# ParallelJoysticks.net
KiCad netlist of a schematic drawn in Altium Designer
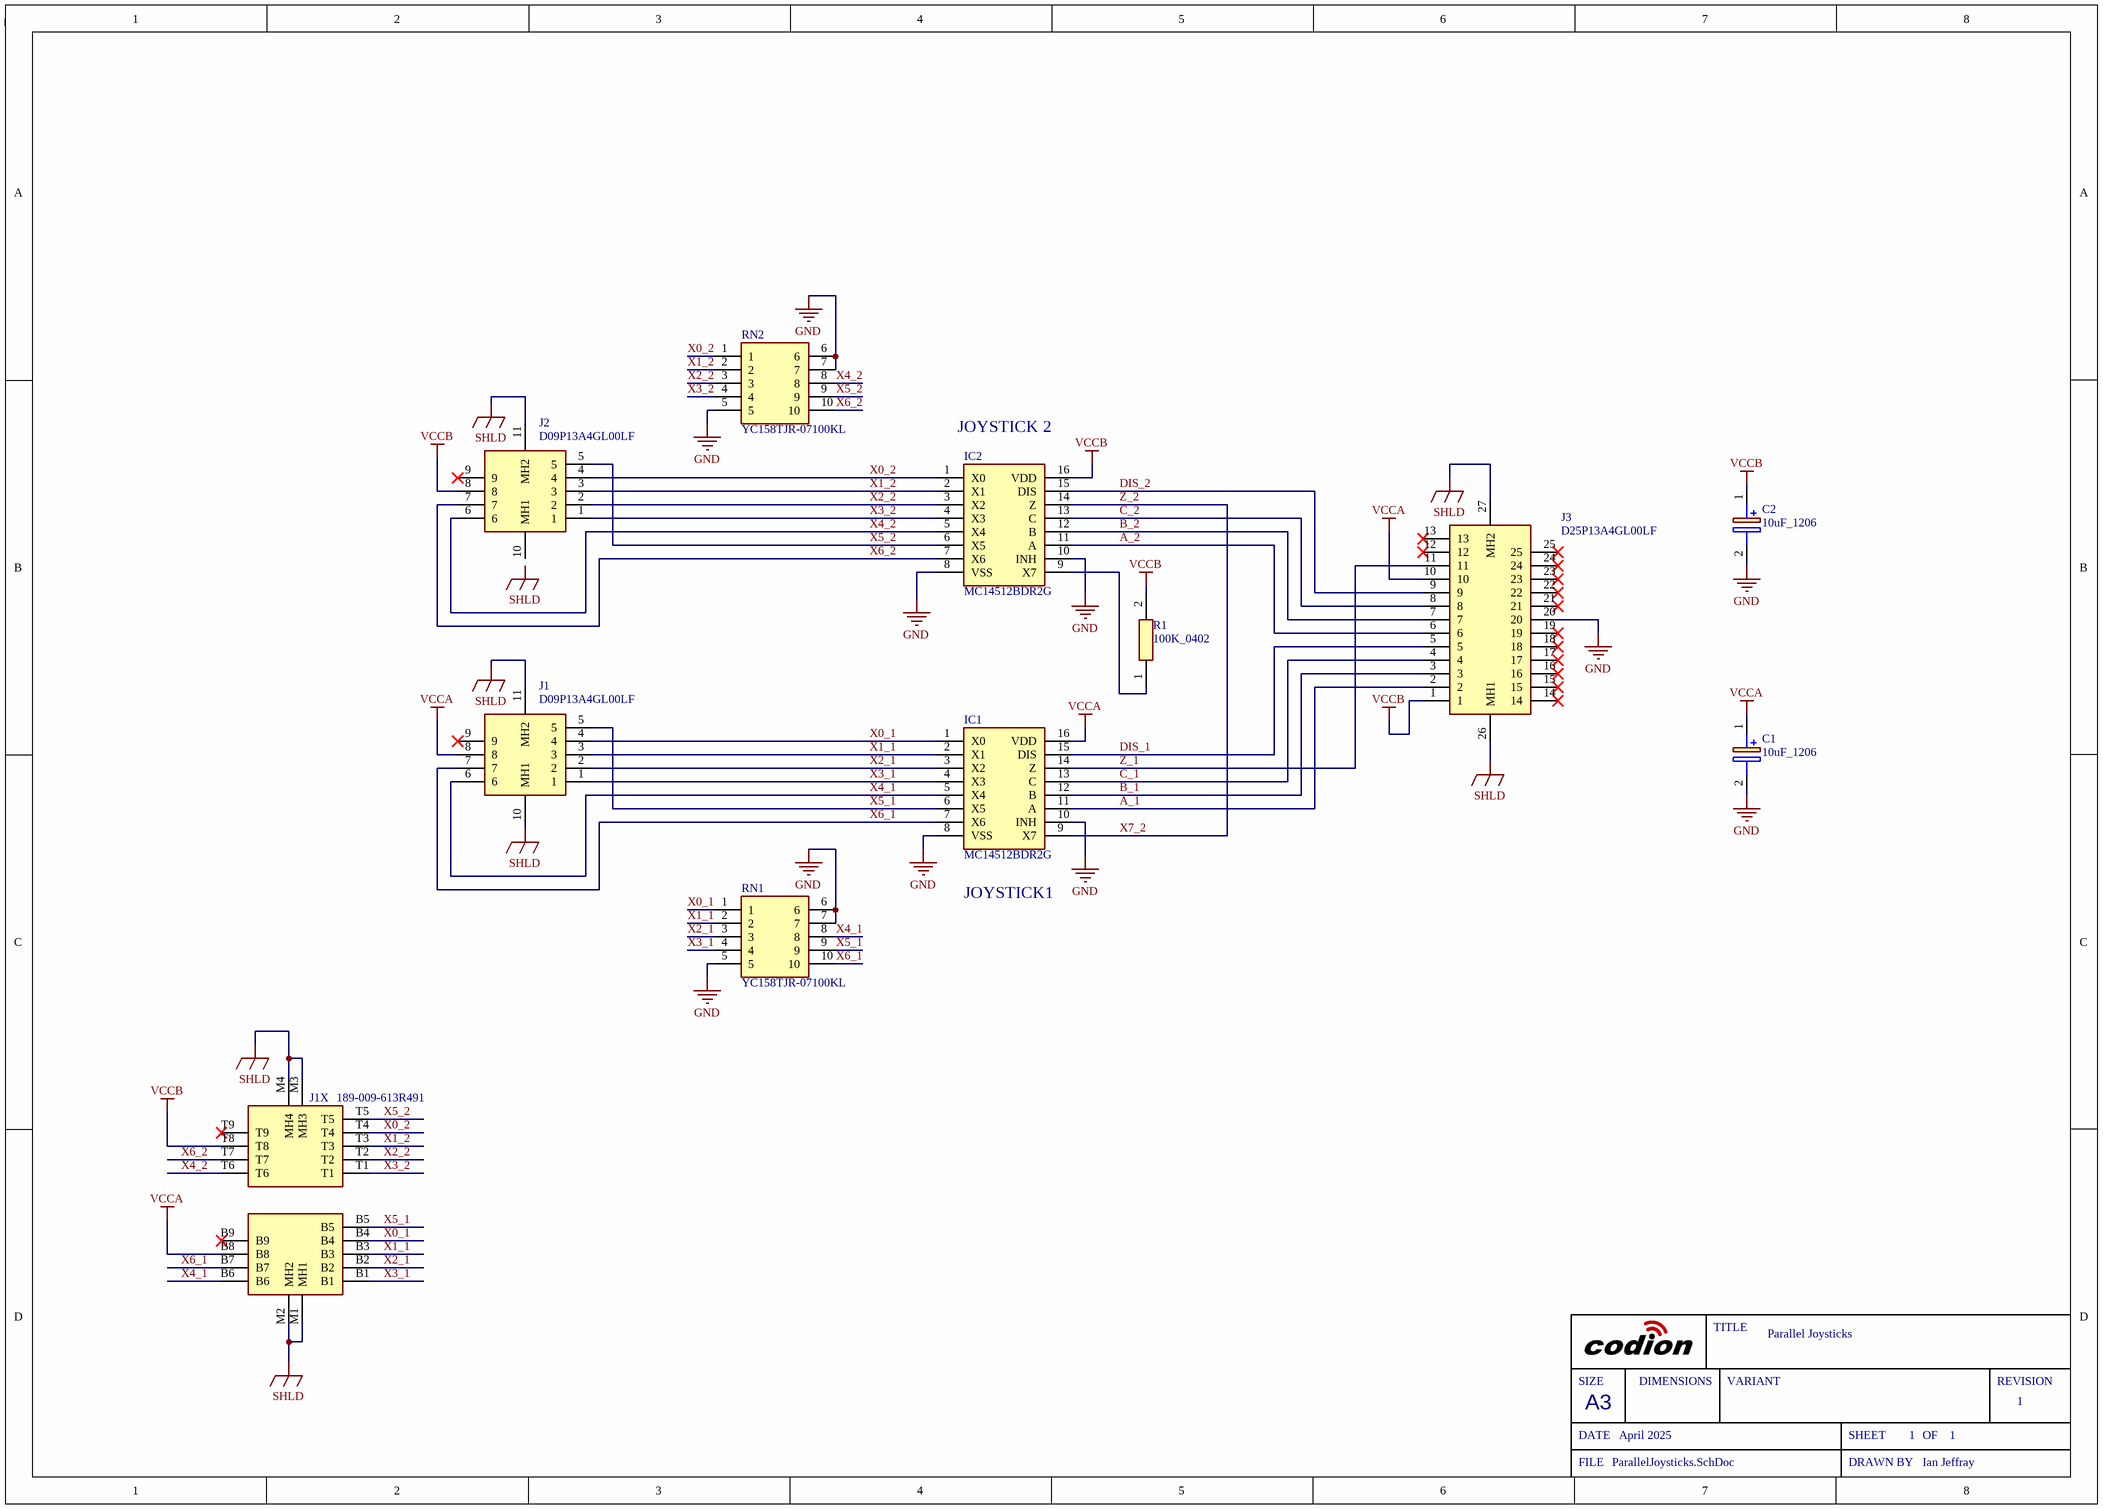
[diagram p0: ParallelJoysticks.SchDoc]

(export (version "E")
  (design (tool "Eeschema 10.0.6"))
  (components
    (comp (ref "C1")
      (value "10uF_1206")
      (footprint "SamacSys:CAPPM3216X180N")
      (description "Capacitor Polarised")
      (fields
        (field (name "MANUFACTURER_PART_NUMBER") "TAJA106M010RNJ")
        (field (name "MOUSER PART NUMBER") "581-TAJA106M010R")
      )
      (libsource (lib "*") (part "TAJA106M010RNJ"))
    )
    (comp (ref "C2")
      (value "10uF_1206")
      (footprint "SamacSys:CAPPM3216X180N")
      (description "Capacitor Polarised")
      (fields
        (field (name "MANUFACTURER_PART_NUMBER") "TAJA106M010RNJ")
        (field (name "MOUSER PART NUMBER") "581-TAJA106M010R")
      )
      (libsource (lib "*") (part "TAJA106M010RNJ"))
    )
    (comp (ref "IC1")
      (value "MC14512BDR2G")
      (footprint "SamacSys:SOIC127P600X175-16N")
      (description "Integrated Circuit")
      (fields (field (name "MOUSER PART NUMBER") "863-MC14512BDR2G"))
      (libsource (lib "*") (part "MC14512BDR2G"))
    )
    (comp (ref "IC2")
      (value "MC14512BDR2G")
      (footprint "SamacSys:SOIC127P600X175-16N")
      (description "Integrated Circuit")
      (fields (field (name "MOUSER PART NUMBER") "863-MC14512BDR2G"))
      (libsource (lib "*") (part "MC14512BDR2G"))
    )
    (comp (ref "J1")
      (value "D09P13A4GL00LF")
      (footprint "SamacSys:D09P13A4GV00LF")
      (description "Connector")
      (libsource (lib "*") (part "D09P13A4GV00LF"))
    )
    (comp (ref "J1X")
      (value "189-009-613R491")
      (footprint "189-009-613R491")
      (description "Connector")
      (libsource (lib "Acorn") (part "189-009-613R491"))
    )
    (comp (ref "J2")
      (value "D09P13A4GL00LF")
      (footprint "SamacSys:D09P13A4GV00LF")
      (description "Connector")
      (libsource (lib "*") (part "D09P13A4GV00LF"))
    )
    (comp (ref "J3")
      (value "D25P13A4GL00LF")
      (footprint "SamacSys:D25P13A4GV00LF")
      (description "Connector")
      (libsource (lib "*") (part "D25P13A4GV00LF"))
    )
    (comp (ref "R1")
      (value "100K_0402")
      (footprint "SamacSys:RESC1005X40N")
      (description "Resistor")
      (fields
        (field (name "MANUFACTURER_PART_NUMBER") "CRCW0402100KFKEDHP")
        (field (name "MOUSER PART NUMBER") "71-CRCW0402100KFKEDH")
      )
      (libsource (lib "*") (part "CRCW0402100KFKEDHP"))
    )
    (comp (ref "RN1")
      (value "YC158TJR-07100KL")
      (footprint "SamacSys:YC158TJR07100KL")
      (description "Resistor Network")
      (fields (field (name "MOUSER PART NUMBER") "603-YC158TJR-07100KL"))
      (libsource (lib "*") (part "YC158TJR-07100KL"))
    )
    (comp (ref "RN2")
      (value "YC158TJR-07100KL")
      (footprint "SamacSys:YC158TJR07100KL")
      (description "Resistor Network")
      (fields (field (name "MOUSER PART NUMBER") "603-YC158TJR-07100KL"))
      (libsource (lib "*") (part "YC158TJR-07100KL"))
    )
  )
  (nets
    (net (code "1") (name "/A_1") (class "Default")
      (node (ref "IC1") (pin "11") (pinfunction "A_11") (pintype "passive"))
      (node (ref "J3") (pin "2") (pinfunction "2_2") (pintype "passive"))
    )
    (net (code "2") (name "/A_2") (class "Default")
      (node (ref "IC2") (pin "11") (pinfunction "A_11") (pintype "passive"))
      (node (ref "J3") (pin "6") (pinfunction "6_6") (pintype "passive"))
    )
    (net (code "3") (name "/B_1") (class "Default")
      (node (ref "IC1") (pin "12") (pinfunction "B_12") (pintype "passive"))
      (node (ref "J3") (pin "3") (pinfunction "3_3") (pintype "passive"))
    )
    (net (code "4") (name "/B_2") (class "Default")
      (node (ref "IC2") (pin "12") (pinfunction "B_12") (pintype "passive"))
      (node (ref "J3") (pin "7") (pinfunction "7_7") (pintype "passive"))
    )
    (net (code "5") (name "/C_1") (class "Default")
      (node (ref "IC1") (pin "13") (pinfunction "C_13") (pintype "passive"))
      (node (ref "J3") (pin "4") (pinfunction "4_4") (pintype "passive"))
    )
    (net (code "6") (name "/C_2") (class "Default")
      (node (ref "IC2") (pin "13") (pinfunction "C_13") (pintype "passive"))
      (node (ref "J3") (pin "8") (pinfunction "8_8") (pintype "passive"))
    )
    (net (code "7") (name "/DIS_1") (class "Default")
      (node (ref "IC1") (pin "15") (pinfunction "DIS_15") (pintype "passive"))
      (node (ref "J3") (pin "5") (pinfunction "5_5") (pintype "passive"))
    )
    (net (code "8") (name "/DIS_2") (class "Default")
      (node (ref "IC2") (pin "15") (pinfunction "DIS_15") (pintype "passive"))
      (node (ref "J3") (pin "9") (pinfunction "9_9") (pintype "passive"))
    )
    (net (code "9") (name "/X0_1") (class "Default")
      (node (ref "IC1") (pin "1") (pinfunction "X0_1") (pintype "passive"))
      (node (ref "J1") (pin "4") (pinfunction "4_4") (pintype "passive"))
      (node (ref "J1X") (pin "B4") (pinfunction "B4_B4") (pintype "passive"))
      (node (ref "RN1") (pin "1") (pinfunction "1_1") (pintype "passive"))
    )
    (net (code "10") (name "/X0_2") (class "Default")
      (node (ref "IC2") (pin "1") (pinfunction "X0_1") (pintype "passive"))
      (node (ref "J1X") (pin "T4") (pinfunction "T4_T4") (pintype "passive"))
      (node (ref "J2") (pin "4") (pinfunction "4_4") (pintype "passive"))
      (node (ref "RN2") (pin "1") (pinfunction "1_1") (pintype "passive"))
    )
    (net (code "11") (name "/X1_1") (class "Default")
      (node (ref "IC1") (pin "2") (pinfunction "X1_2") (pintype "passive"))
      (node (ref "J1") (pin "3") (pinfunction "3_3") (pintype "passive"))
      (node (ref "J1X") (pin "B3") (pinfunction "B3_B3") (pintype "passive"))
      (node (ref "RN1") (pin "2") (pinfunction "2_2") (pintype "passive"))
    )
    (net (code "12") (name "/X1_2") (class "Default")
      (node (ref "IC2") (pin "2") (pinfunction "X1_2") (pintype "passive"))
      (node (ref "J1X") (pin "T3") (pinfunction "T3_T3") (pintype "passive"))
      (node (ref "J2") (pin "3") (pinfunction "3_3") (pintype "passive"))
      (node (ref "RN2") (pin "2") (pinfunction "2_2") (pintype "passive"))
    )
    (net (code "13") (name "/X2_1") (class "Default")
      (node (ref "IC1") (pin "3") (pinfunction "X2_3") (pintype "passive"))
      (node (ref "J1") (pin "2") (pinfunction "2_2") (pintype "passive"))
      (node (ref "J1X") (pin "B2") (pinfunction "B2_B2") (pintype "passive"))
      (node (ref "RN1") (pin "3") (pinfunction "3_3") (pintype "passive"))
    )
    (net (code "14") (name "/X2_2") (class "Default")
      (node (ref "IC2") (pin "3") (pinfunction "X2_3") (pintype "passive"))
      (node (ref "J1X") (pin "T2") (pinfunction "T2_T2") (pintype "passive"))
      (node (ref "J2") (pin "2") (pinfunction "2_2") (pintype "passive"))
      (node (ref "RN2") (pin "3") (pinfunction "3_3") (pintype "passive"))
    )
    (net (code "15") (name "/X3_1") (class "Default")
      (node (ref "IC1") (pin "4") (pinfunction "X3_4") (pintype "passive"))
      (node (ref "J1") (pin "1") (pinfunction "1_1") (pintype "passive"))
      (node (ref "J1X") (pin "B1") (pinfunction "B1_B1") (pintype "passive"))
      (node (ref "RN1") (pin "4") (pinfunction "4_4") (pintype "passive"))
    )
    (net (code "16") (name "/X3_2") (class "Default")
      (node (ref "IC2") (pin "4") (pinfunction "X3_4") (pintype "passive"))
      (node (ref "J1X") (pin "T1") (pinfunction "T1_T1") (pintype "passive"))
      (node (ref "J2") (pin "1") (pinfunction "1_1") (pintype "passive"))
      (node (ref "RN2") (pin "4") (pinfunction "4_4") (pintype "passive"))
    )
    (net (code "17") (name "/X4_1") (class "Default")
      (node (ref "IC1") (pin "5") (pinfunction "X4_5") (pintype "passive"))
      (node (ref "J1") (pin "6") (pinfunction "6_6") (pintype "passive"))
      (node (ref "J1X") (pin "B6") (pinfunction "B6_B6") (pintype "passive"))
      (node (ref "RN1") (pin "8") (pinfunction "8_8") (pintype "passive"))
    )
    (net (code "18") (name "/X4_2") (class "Default")
      (node (ref "IC2") (pin "5") (pinfunction "X4_5") (pintype "passive"))
      (node (ref "J1X") (pin "T6") (pinfunction "T6_T6") (pintype "passive"))
      (node (ref "J2") (pin "6") (pinfunction "6_6") (pintype "passive"))
      (node (ref "RN2") (pin "8") (pinfunction "8_8") (pintype "passive"))
    )
    (net (code "19") (name "/X5_1") (class "Default")
      (node (ref "IC1") (pin "6") (pinfunction "X5_6") (pintype "passive"))
      (node (ref "J1") (pin "5") (pinfunction "5_5") (pintype "passive"))
      (node (ref "J1X") (pin "B5") (pinfunction "B5_B5") (pintype "passive"))
      (node (ref "RN1") (pin "9") (pinfunction "9_9") (pintype "passive"))
    )
    (net (code "20") (name "/X5_2") (class "Default")
      (node (ref "IC2") (pin "6") (pinfunction "X5_6") (pintype "passive"))
      (node (ref "J1X") (pin "T5") (pinfunction "T5_T5") (pintype "passive"))
      (node (ref "J2") (pin "5") (pinfunction "5_5") (pintype "passive"))
      (node (ref "RN2") (pin "9") (pinfunction "9_9") (pintype "passive"))
    )
    (net (code "21") (name "/X6_1") (class "Default")
      (node (ref "IC1") (pin "7") (pinfunction "X6_7") (pintype "passive"))
      (node (ref "J1") (pin "7") (pinfunction "7_7") (pintype "passive"))
      (node (ref "J1X") (pin "B7") (pinfunction "B7_B7") (pintype "passive"))
      (node (ref "RN1") (pin "10") (pinfunction "10_10") (pintype "passive"))
    )
    (net (code "22") (name "/X6_2") (class "Default")
      (node (ref "IC2") (pin "7") (pinfunction "X6_7") (pintype "passive"))
      (node (ref "J1X") (pin "T7") (pinfunction "T7_T7") (pintype "passive"))
      (node (ref "J2") (pin "7") (pinfunction "7_7") (pintype "passive"))
      (node (ref "RN2") (pin "10") (pinfunction "10_10") (pintype "passive"))
    )
    (net (code "23") (name "/X7_2") (class "Default")
      (node (ref "IC1") (pin "9") (pinfunction "X7_9") (pintype "passive"))
      (node (ref "IC2") (pin "14") (pinfunction "Z_14") (pintype "passive"))
    )
    (net (code "24") (name "/Z_1") (class "Default")
      (node (ref "IC1") (pin "14") (pinfunction "Z_14") (pintype "passive"))
      (node (ref "J3") (pin "11") (pinfunction "11_11") (pintype "passive"))
    )
    (net (code "25") (name "GND") (class "Default")
      (node (ref "C1") (pin "2") (pinfunction "-_2") (pintype "passive"))
      (node (ref "C2") (pin "2") (pinfunction "-_2") (pintype "passive"))
      (node (ref "IC1") (pin "10") (pinfunction "INH_10") (pintype "passive"))
      (node (ref "IC1") (pin "8") (pinfunction "VSS_8") (pintype "passive"))
      (node (ref "IC2") (pin "10") (pinfunction "INH_10") (pintype "passive"))
      (node (ref "IC2") (pin "8") (pinfunction "VSS_8") (pintype "passive"))
      (node (ref "J3") (pin "20") (pinfunction "20_20") (pintype "passive"))
      (node (ref "RN1") (pin "5") (pinfunction "5_5") (pintype "passive"))
      (node (ref "RN1") (pin "6") (pinfunction "6_6") (pintype "passive"))
      (node (ref "RN1") (pin "7") (pinfunction "7_7") (pintype "passive"))
      (node (ref "RN2") (pin "5") (pinfunction "5_5") (pintype "passive"))
      (node (ref "RN2") (pin "6") (pinfunction "6_6") (pintype "passive"))
      (node (ref "RN2") (pin "7") (pinfunction "7_7") (pintype "passive"))
    )
    (net (code "26") (name "Net-(IC2-X7)") (class "Default")
      (node (ref "IC2") (pin "9") (pinfunction "X7_9") (pintype "passive"))
      (node (ref "R1") (pin "1") (pinfunction "1_1") (pintype "passive"))
    )
    (net (code "27") (name "SHLD") (class "Default")
      (node (ref "J1") (pin "10") (pinfunction "MH1_10") (pintype "passive"))
      (node (ref "J1") (pin "11") (pinfunction "MH2_11") (pintype "passive"))
      (node (ref "J1X") (pin "M1") (pinfunction "MH1_M1") (pintype "passive"))
      (node (ref "J1X") (pin "M2") (pinfunction "MH2_M2") (pintype "passive"))
      (node (ref "J1X") (pin "M3") (pinfunction "MH3_M3") (pintype "passive"))
      (node (ref "J1X") (pin "M4") (pinfunction "MH4_M4") (pintype "passive"))
      (node (ref "J2") (pin "11") (pinfunction "MH2_11") (pintype "passive"))
      (node (ref "J3") (pin "26") (pinfunction "MH1_26") (pintype "passive"))
      (node (ref "J3") (pin "27") (pinfunction "MH2_27") (pintype "passive"))
    )
    (net (code "28") (name "VCCA") (class "Default")
      (node (ref "C1") (pin "1") (pinfunction "+_1") (pintype "passive"))
      (node (ref "IC1") (pin "16") (pinfunction "VDD_16") (pintype "passive"))
      (node (ref "J1") (pin "8") (pinfunction "8_8") (pintype "passive"))
      (node (ref "J1X") (pin "B8") (pinfunction "B8_B8") (pintype "passive"))
      (node (ref "J3") (pin "10") (pinfunction "10_10") (pintype "passive"))
    )
    (net (code "29") (name "VCCB") (class "Default")
      (node (ref "C2") (pin "1") (pinfunction "+_1") (pintype "passive"))
      (node (ref "IC2") (pin "16") (pinfunction "VDD_16") (pintype "passive"))
      (node (ref "J1X") (pin "T8") (pinfunction "T8_T8") (pintype "passive"))
      (node (ref "J2") (pin "8") (pinfunction "8_8") (pintype "passive"))
      (node (ref "J3") (pin "1") (pinfunction "1_1") (pintype "passive"))
      (node (ref "R1") (pin "2") (pinfunction "2_2") (pintype "passive"))
    )
    (net (code "30") (name "unconnected-(J1-Pad9)") (class "Default")
      (node (ref "J1") (pin "9") (pinfunction "9_9") (pintype "passive+no_connect"))
    )
    (net (code "31") (name "unconnected-(J1X-PadB9)") (class "Default")
      (node (ref "J1X") (pin "B9") (pinfunction "B9_B9") (pintype "passive+no_connect"))
    )
    (net (code "32") (name "unconnected-(J1X-PadT9)") (class "Default")
      (node (ref "J1X") (pin "T9") (pinfunction "T9_T9") (pintype "passive+no_connect"))
    )
    (net (code "33") (name "unconnected-(J2-MH1-Pad10)") (class "Default")
      (node (ref "J2") (pin "10") (pinfunction "MH1_10") (pintype "passive"))
    )
    (net (code "34") (name "unconnected-(J2-Pad9)") (class "Default")
      (node (ref "J2") (pin "9") (pinfunction "9_9") (pintype "passive+no_connect"))
    )
    (net (code "35") (name "unconnected-(J3-Pad12)") (class "Default")
      (node (ref "J3") (pin "12") (pinfunction "12_12") (pintype "passive+no_connect"))
    )
    (net (code "36") (name "unconnected-(J3-Pad13)") (class "Default")
      (node (ref "J3") (pin "13") (pinfunction "13_13") (pintype "passive+no_connect"))
    )
    (net (code "37") (name "unconnected-(J3-Pad14)") (class "Default")
      (node (ref "J3") (pin "14") (pinfunction "14_14") (pintype "passive+no_connect"))
    )
    (net (code "38") (name "unconnected-(J3-Pad15)") (class "Default")
      (node (ref "J3") (pin "15") (pinfunction "15_15") (pintype "passive+no_connect"))
    )
    (net (code "39") (name "unconnected-(J3-Pad16)") (class "Default")
      (node (ref "J3") (pin "16") (pinfunction "16_16") (pintype "passive+no_connect"))
    )
    (net (code "40") (name "unconnected-(J3-Pad17)") (class "Default")
      (node (ref "J3") (pin "17") (pinfunction "17_17") (pintype "passive+no_connect"))
    )
    (net (code "41") (name "unconnected-(J3-Pad18)") (class "Default")
      (node (ref "J3") (pin "18") (pinfunction "18_18") (pintype "passive+no_connect"))
    )
    (net (code "42") (name "unconnected-(J3-Pad19)") (class "Default")
      (node (ref "J3") (pin "19") (pinfunction "19_19") (pintype "passive+no_connect"))
    )
    (net (code "43") (name "unconnected-(J3-Pad21)") (class "Default")
      (node (ref "J3") (pin "21") (pinfunction "21_21") (pintype "passive+no_connect"))
    )
    (net (code "44") (name "unconnected-(J3-Pad22)") (class "Default")
      (node (ref "J3") (pin "22") (pinfunction "22_22") (pintype "passive+no_connect"))
    )
    (net (code "45") (name "unconnected-(J3-Pad23)") (class "Default")
      (node (ref "J3") (pin "23") (pinfunction "23_23") (pintype "passive+no_connect"))
    )
    (net (code "46") (name "unconnected-(J3-Pad24)") (class "Default")
      (node (ref "J3") (pin "24") (pinfunction "24_24") (pintype "passive+no_connect"))
    )
    (net (code "47") (name "unconnected-(J3-Pad25)") (class "Default")
      (node (ref "J3") (pin "25") (pinfunction "25_25") (pintype "passive+no_connect"))
    )
  )
)
